# Central_Unit.net
KiCad netlist of a schematic drawn in Altium Designer
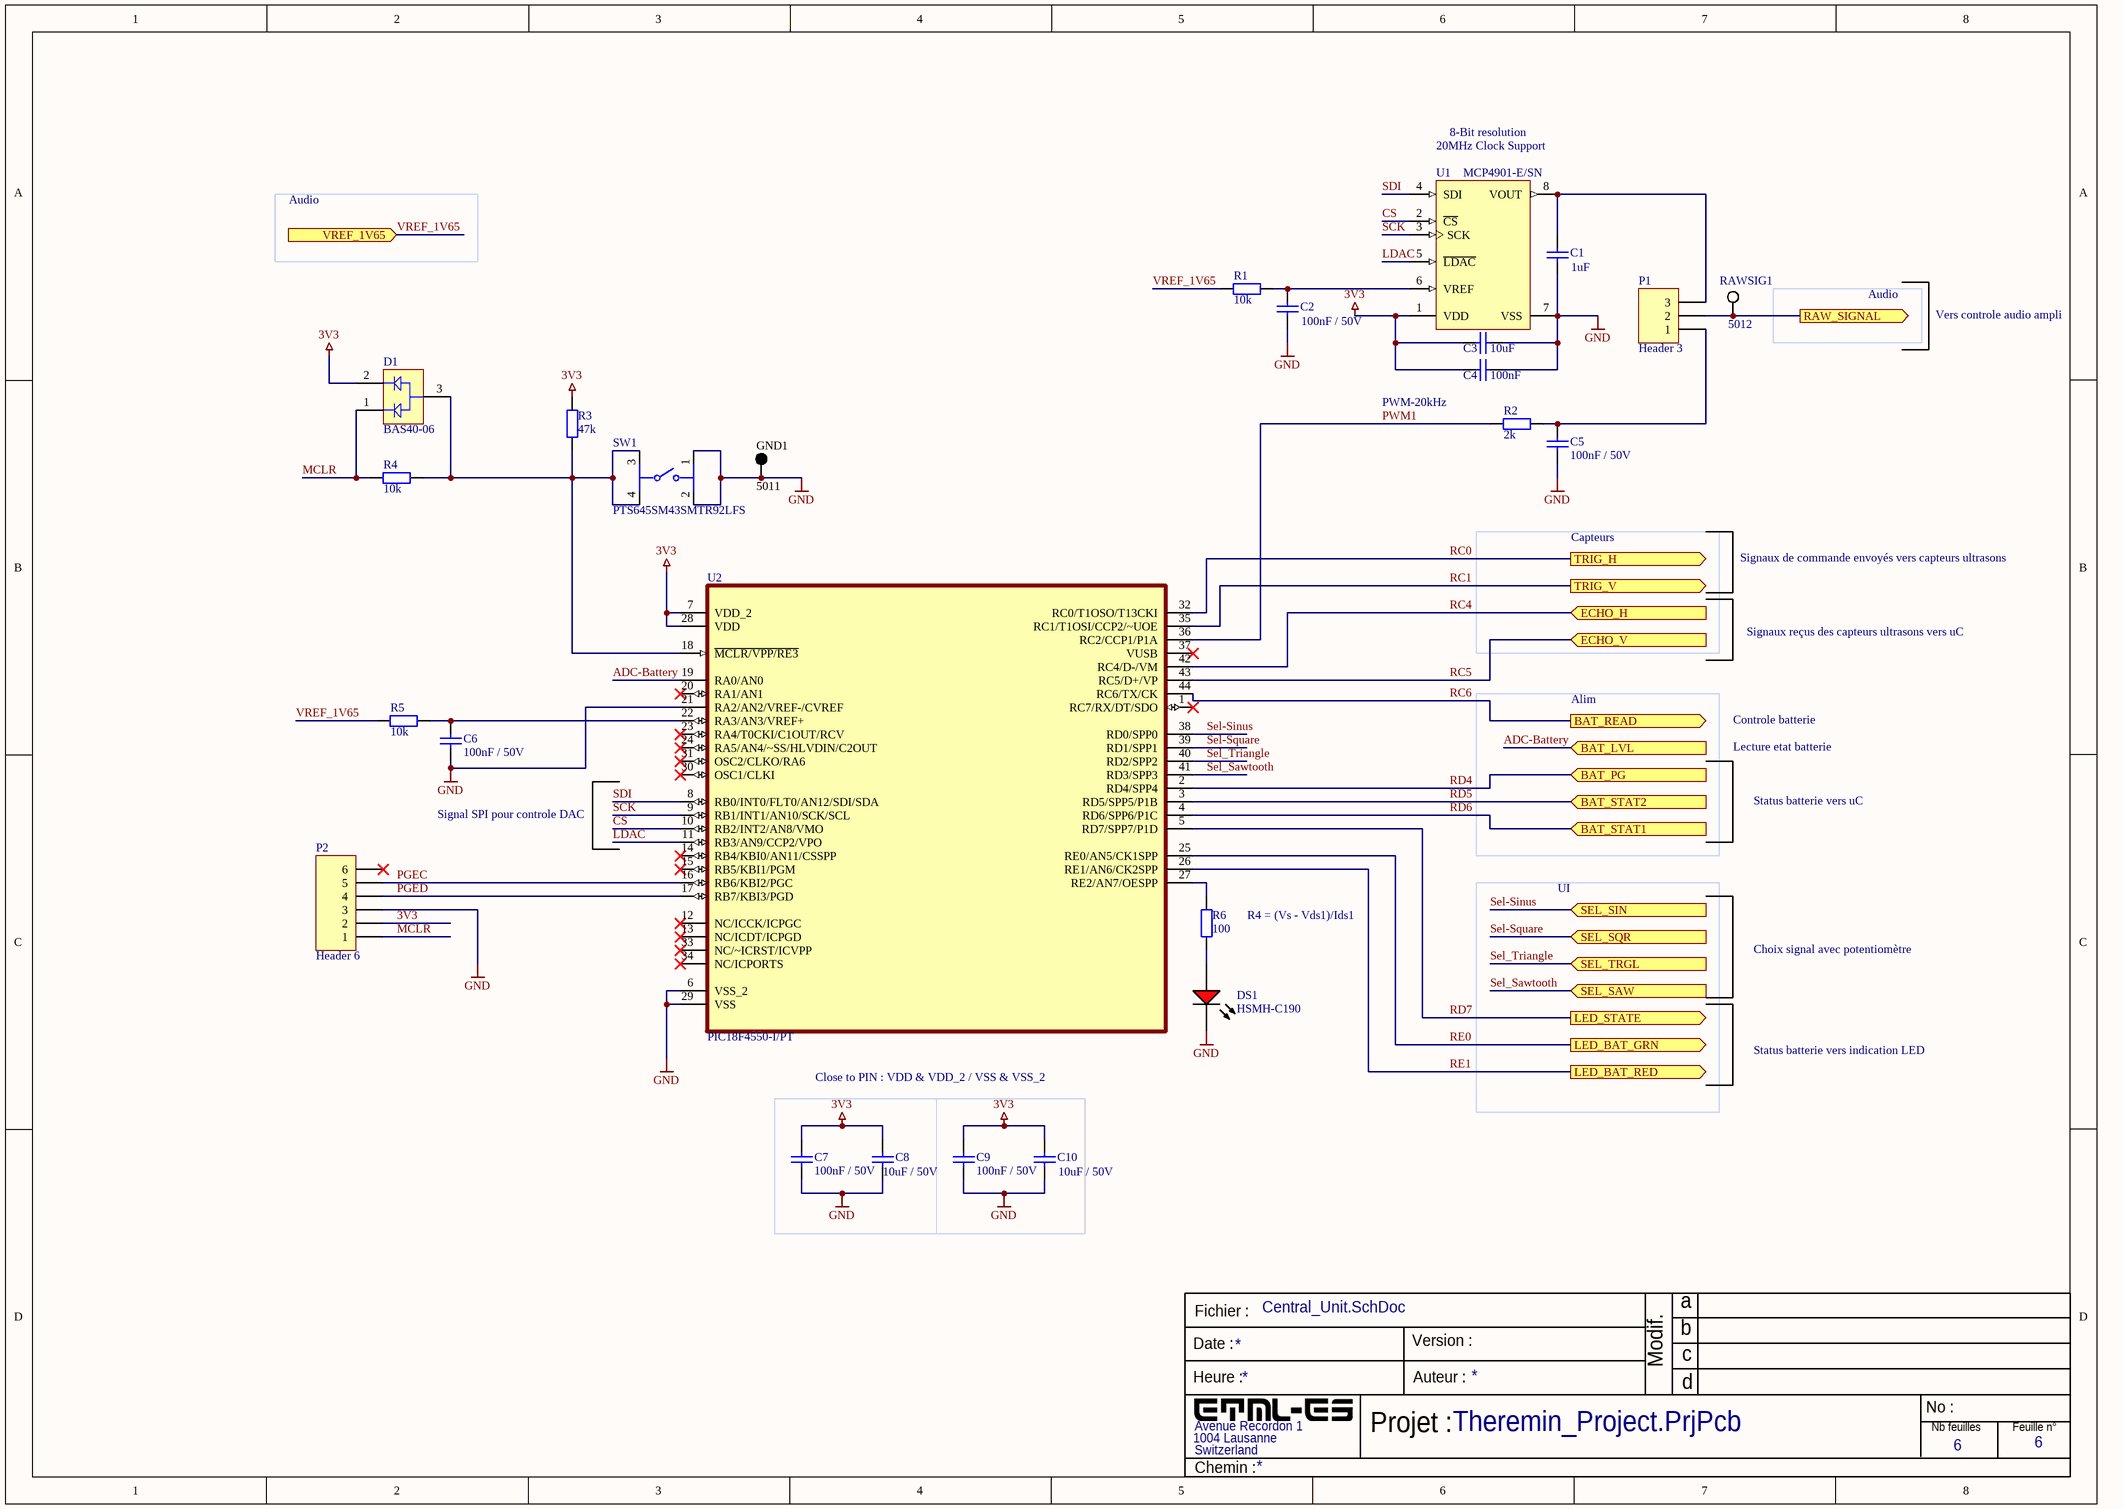
[diagram p0: Central_Unit.SchDoc]

(export (version "E")
  (design (tool "Eeschema 10.0.6"))
  (components
    (comp (ref "C1")
      (value "1uF")
      (footprint "CAPC0805")
      (description "Capacitor")
      (fields (field (name "PUBLISHER") "Altium Limited"))
      (libsource (lib "Miscellaneous Devices") (part "Cap"))
    )
    (comp (ref "C2")
      (value "100nF / 50V")
      (footprint "CAPC0805")
      (description "Capacitor")
      (fields (field (name "PUBLISHER") "Altium Limited"))
      (libsource (lib "Miscellaneous Devices") (part "Cap"))
    )
    (comp (ref "C3")
      (value "10uF")
      (footprint "CAPC0805")
      (description "Capacitor")
      (fields (field (name "PUBLISHER") "Altium Limited"))
      (libsource (lib "Miscellaneous Devices") (part "Cap"))
    )
    (comp (ref "C4")
      (value "100nF")
      (footprint "CAPC0805")
      (description "Capacitor")
      (fields (field (name "PUBLISHER") "Altium Limited"))
      (libsource (lib "Miscellaneous Devices") (part "Cap"))
    )
    (comp (ref "C5")
      (value "100nF / 50V")
      (footprint "CAPC0805")
      (description "Capacitor")
      (fields (field (name "PUBLISHER") "Altium Limited"))
      (libsource (lib "Miscellaneous Devices") (part "Cap"))
    )
    (comp (ref "C6")
      (value "100nF / 50V")
      (footprint "CAPC0805")
      (description "Capacitor")
      (fields (field (name "PUBLISHER") "Altium Limited"))
      (libsource (lib "Miscellaneous Devices") (part "Cap"))
    )
    (comp (ref "C7")
      (value "100nF / 50V")
      (footprint "CAPC0805")
      (description "Capacitor")
      (fields (field (name "PUBLISHER") "Altium Limited"))
      (libsource (lib "Miscellaneous Devices") (part "Cap"))
    )
    (comp (ref "C8")
      (value "10uF / 50V")
      (footprint "CAPC0805")
      (description "Capacitor")
      (fields (field (name "PUBLISHER") "Altium Limited"))
      (libsource (lib "Miscellaneous Devices") (part "Cap"))
    )
    (comp (ref "C9")
      (value "100nF / 50V")
      (footprint "CAPC0805")
      (description "Capacitor")
      (fields (field (name "PUBLISHER") "Altium Limited"))
      (libsource (lib "Miscellaneous Devices") (part "Cap"))
    )
    (comp (ref "C10")
      (value "10uF / 50V")
      (footprint "CAPC0805")
      (description "Capacitor")
      (fields (field (name "PUBLISHER") "Altium Limited"))
      (libsource (lib "Miscellaneous Devices") (part "Cap"))
    )
    (comp (ref "D1")
      (value "BAS40-06")
      (footprint "INF-SOT23_M")
      (description "Silicon Schottky Diode, -55 to 150 degC, SOT23, Reel, Green")
      (fields (field (name "MANUFACTURER") "Infineon"))
      (libsource (lib "Altium Content Vault") (part "INF-D_K1K2A3-3"))
    )
    (comp (ref "DS1")
      (value "HSMH-C190")
      (footprint "AVAG-HSMX-C190_V")
      (description "LED Uni-Color Red, 65 mW, 20 mA, -40 to 85 degC, 2-Pin SMD, RoHS, Tape and Reel")
      (libsource (lib "Altium Content Vault") (part "LED-RED-AK-2"))
    )
    (comp (ref "GND1")
      (value "5011")
      (footprint "KSTN-5011_V")
      (description "Test Point, Black, Through Hole, RoHS, Bulk")
      (fields (field (name "MANUFACTURER") "Keystone"))
      (libsource (lib "Altium Content Vault") (part "TESTPOINT_BLACK"))
    )
    (comp (ref "P1")
      (value "Header 3")
      (footprint "PIN-1x03_2.54")
      (description "Header, 3-Pin")
      (fields (field (name "PUBLISHER") "Altium Limited"))
      (libsource (lib "Miscellaneous Connectors") (part "Header 3"))
    )
    (comp (ref "P2")
      (value "Header 6")
      (footprint "PIN-1x06_2.54")
      (description "Header, 6-Pin")
      (fields (field (name "PUBLISHER") "Altium Limited"))
      (libsource (lib "Miscellaneous Connectors") (part "Header 6"))
    )
    (comp (ref "R1")
      (value "10k")
      (footprint "RESC0805")
      (description "Resistor")
      (libsource (lib "Support_BAT_1043") (part "RES"))
    )
    (comp (ref "R2")
      (value "2k")
      (footprint "RESC0805")
      (description "Resistor")
      (libsource (lib "Support_BAT_1043") (part "RES"))
    )
    (comp (ref "R3")
      (value "47k")
      (footprint "RESC0805")
      (description "Resistor")
      (libsource (lib "") (part "RES_1"))
    )
    (comp (ref "R4")
      (value "10k")
      (footprint "RESC0805")
      (description "Resistor")
      (libsource (lib "Support_BAT_1043") (part "RES"))
    )
    (comp (ref "R5")
      (value "10k")
      (footprint "RESC0805")
      (description "Resistor")
      (libsource (lib "Support_BAT_1043") (part "RES"))
    )
    (comp (ref "R6")
      (value "100")
      (footprint "RESC0805")
      (description "Resistor")
      (libsource (lib "") (part "RES_1"))
    )
    (comp (ref "RAWSIG1")
      (value "5012")
      (footprint "KSTN-5012_V")
      (description "Test Point, White, Through Hole, RoHS, Bulk")
      (fields (field (name "MANUFACTURER") "Keystone"))
      (libsource (lib "Altium Content Vault") (part "TESTPOINT_WHITE"))
    )
    (comp (ref "SW1")
      (value "PTS645SM43SMTR92LFS")
      (footprint "FP-PTS645SM43SMTR92LFS-MFG")
      (description "SWITCH TACTILE SPST-NO 0.05A 12V")
      (libsource (lib "Altium Content Vault") (part "1adf0dd01260c80cf25a44bfd6b99ba"))
    )
    (comp (ref "U1")
      (value "MCP4901-E/SN")
      (footprint "SOIC-SN8_N")
      (description "8-Bit DAC with SPI Interface, 8-Pin SOIC 150mil, Extended Temperature")
      (libsource (lib "Altium Content Vault") (part "CON-DAC-MCP4921-8"))
    )
    (comp (ref "U2")
      (value "PIC18F4550-I/PT")
      (footprint "TQFP80P1200X1200X120-44M")
      (description "PIC PICÂ® 18F Microcontroller IC 8-Bit 48MHz 32KB _16K x 16_ FLASH 44-TQFP _10x10_")
      (fields (field (name "MF") "Microchip"))
      (libsource (lib "PIC18F4550-I_PT") (part "PIC18F4550-I/PT"))
    )
  )
  (nets
    (net (code "1") (name "/ADC-Battery") (class "Default")
      (node (ref "U2") (pin "19") (pinfunction "RA0/AN0_19") (pintype "passive"))
    )
    (net (code "2") (name "/CS") (class "Default")
      (node (ref "U1") (pin "2") (pinfunction "~{CS}_2") (pintype "input"))
      (node (ref "U2") (pin "10") (pinfunction "RB2/INT2/AN8/VMO_10") (pintype "bidirectional"))
    )
    (net (code "3") (name "/LDAC") (class "Default")
      (node (ref "U1") (pin "5") (pinfunction "~{LDAC}_5") (pintype "input"))
      (node (ref "U2") (pin "11") (pinfunction "RB3/AN9/CCP2/VPO_11") (pintype "bidirectional"))
    )
    (net (code "4") (name "/MCLR") (class "Default")
      (node (ref "D1") (pin "1") (pinfunction "K1_1") (pintype "passive"))
      (node (ref "P2") (pin "1") (pinfunction "1_1") (pintype "passive"))
      (node (ref "R4") (pin "2") (pinfunction "2_2") (pintype "passive"))
    )
    (net (code "5") (name "/PGEC") (class "Default")
      (node (ref "P2") (pin "5") (pinfunction "5_5") (pintype "passive"))
      (node (ref "U2") (pin "16") (pinfunction "RB6/KBI2/PGC_16") (pintype "bidirectional"))
    )
    (net (code "6") (name "/PGED") (class "Default")
      (node (ref "P2") (pin "4") (pinfunction "4_4") (pintype "passive"))
      (node (ref "U2") (pin "17") (pinfunction "RB7/KBI3/PGD_17") (pintype "bidirectional"))
    )
    (net (code "7") (name "/PWM1") (class "Default")
      (node (ref "R2") (pin "2") (pinfunction "2_2") (pintype "passive"))
      (node (ref "U2") (pin "36") (pinfunction "RC2/CCP1/P1A_36") (pintype "passive"))
    )
    (net (code "8") (name "/RAW_SIGNAL") (class "Default")
      (node (ref "P1") (pin "2") (pinfunction "2_2") (pintype "passive"))
      (node (ref "RAWSIG1") (pin "1") (pinfunction "1_1") (pintype "passive"))
    )
    (net (code "9") (name "/RC0") (class "Default")
      (node (ref "U2") (pin "32") (pinfunction "RC0/T1OSO/T13CKI_32") (pintype "passive"))
    )
    (net (code "10") (name "/RC1") (class "Default")
      (node (ref "U2") (pin "35") (pinfunction "RC1/T1OSI/CCP2/~UOE_35") (pintype "passive"))
    )
    (net (code "11") (name "/RC4") (class "Default")
      (node (ref "U2") (pin "42") (pinfunction "RC4/D-/VM_42") (pintype "passive"))
    )
    (net (code "12") (name "/RC5") (class "Default")
      (node (ref "U2") (pin "43") (pinfunction "RC5/D+/VP_43") (pintype "passive"))
    )
    (net (code "13") (name "/RC6") (class "Default")
      (node (ref "U2") (pin "44") (pinfunction "RC6/TX/CK_44") (pintype "passive"))
    )
    (net (code "14") (name "/RD4") (class "Default")
      (node (ref "U2") (pin "2") (pinfunction "RD4/SPP4_2") (pintype "passive"))
    )
    (net (code "15") (name "/RD5") (class "Default")
      (node (ref "U2") (pin "3") (pinfunction "RD5/SPP5/P1B_3") (pintype "passive"))
    )
    (net (code "16") (name "/RD6") (class "Default")
      (node (ref "U2") (pin "4") (pinfunction "RD6/SPP6/P1C_4") (pintype "passive"))
    )
    (net (code "17") (name "/RD7") (class "Default")
      (node (ref "U2") (pin "5") (pinfunction "RD7/SPP7/P1D_5") (pintype "passive"))
    )
    (net (code "18") (name "/RE0") (class "Default")
      (node (ref "U2") (pin "25") (pinfunction "RE0/AN5/CK1SPP_25") (pintype "passive"))
    )
    (net (code "19") (name "/RE1") (class "Default")
      (node (ref "U2") (pin "26") (pinfunction "RE1/AN6/CK2SPP_26") (pintype "passive"))
    )
    (net (code "20") (name "/SCK") (class "Default")
      (node (ref "U1") (pin "3") (pinfunction "SCK_3") (pintype "input"))
      (node (ref "U2") (pin "9") (pinfunction "RB1/INT1/AN10/SCK/SCL_9") (pintype "bidirectional"))
    )
    (net (code "21") (name "/SDI") (class "Default")
      (node (ref "U1") (pin "4") (pinfunction "SDI_4") (pintype "input"))
      (node (ref "U2") (pin "8") (pinfunction "RB0/INT0/FLT0/AN12/SDI/SDA_8") (pintype "bidirectional"))
    )
    (net (code "22") (name "/Sel-Sinus") (class "Default")
      (node (ref "U2") (pin "38") (pinfunction "RD0/SPP0_38") (pintype "passive"))
    )
    (net (code "23") (name "/Sel-Square") (class "Default")
      (node (ref "U2") (pin "39") (pinfunction "RD1/SPP1_39") (pintype "passive"))
    )
    (net (code "24") (name "/Sel_Sawtooth") (class "Default")
      (node (ref "U2") (pin "41") (pinfunction "RD3/SPP3_41") (pintype "passive"))
    )
    (net (code "25") (name "/Sel_Triangle") (class "Default")
      (node (ref "U2") (pin "40") (pinfunction "RD2/SPP2_40") (pintype "passive"))
    )
    (net (code "26") (name "/VREF_1V65") (class "Default")
      (node (ref "R1") (pin "2") (pinfunction "2_2") (pintype "passive"))
      (node (ref "R5") (pin "2") (pinfunction "2_2") (pintype "passive"))
    )
    (net (code "27") (name "3V3") (class "Default")
      (node (ref "C10") (pin "1") (pinfunction "1_1") (pintype "passive"))
      (node (ref "C3") (pin "1") (pinfunction "1_1") (pintype "passive"))
      (node (ref "C4") (pin "1") (pinfunction "1_1") (pintype "passive"))
      (node (ref "C7") (pin "1") (pinfunction "1_1") (pintype "passive"))
      (node (ref "C8") (pin "1") (pinfunction "1_1") (pintype "passive"))
      (node (ref "C9") (pin "1") (pinfunction "1_1") (pintype "passive"))
      (node (ref "D1") (pin "2") (pinfunction "K2_2") (pintype "passive"))
      (node (ref "P2") (pin "2") (pinfunction "2_2") (pintype "passive"))
      (node (ref "R3") (pin "1") (pinfunction "1_1") (pintype "passive"))
      (node (ref "U1") (pin "1") (pinfunction "VDD_1") (pintype "power_in"))
      (node (ref "U2") (pin "28") (pinfunction "VDD_28") (pintype "power_in"))
      (node (ref "U2") (pin "7") (pinfunction "VDD_2_7") (pintype "power_in"))
    )
    (net (code "28") (name "GND") (class "Default")
      (node (ref "C1") (pin "2") (pinfunction "2_2") (pintype "passive"))
      (node (ref "C10") (pin "2") (pinfunction "2_2") (pintype "passive"))
      (node (ref "C2") (pin "2") (pinfunction "2_2") (pintype "passive"))
      (node (ref "C3") (pin "2") (pinfunction "2_2") (pintype "passive"))
      (node (ref "C4") (pin "2") (pinfunction "2_2") (pintype "passive"))
      (node (ref "C5") (pin "2") (pinfunction "2_2") (pintype "passive"))
      (node (ref "C6") (pin "2") (pinfunction "2_2") (pintype "passive"))
      (node (ref "C7") (pin "2") (pinfunction "2_2") (pintype "passive"))
      (node (ref "C8") (pin "2") (pinfunction "2_2") (pintype "passive"))
      (node (ref "C9") (pin "2") (pinfunction "2_2") (pintype "passive"))
      (node (ref "DS1") (pin "2") (pinfunction "K_2") (pintype "passive"))
      (node (ref "GND1") (pin "1") (pinfunction "1_1") (pintype "passive"))
      (node (ref "P2") (pin "3") (pinfunction "3_3") (pintype "passive"))
      (node (ref "SW1") (pin "1") (pinfunction "1_1") (pintype "passive"))
      (node (ref "SW1") (pin "2") (pinfunction "2_2") (pintype "passive"))
      (node (ref "U1") (pin "7") (pinfunction "VSS_7") (pintype "power_in"))
      (node (ref "U2") (pin "21") (pinfunction "RA2/AN2/VREF-/CVREF_21") (pintype "passive"))
      (node (ref "U2") (pin "29") (pinfunction "VSS_29") (pintype "power_in"))
      (node (ref "U2") (pin "6") (pinfunction "VSS_2_6") (pintype "power_in"))
    )
    (net (code "29") (name "Net-(C5-Pad1)") (class "Default")
      (node (ref "C5") (pin "1") (pinfunction "1_1") (pintype "passive"))
      (node (ref "P1") (pin "1") (pinfunction "1_1") (pintype "passive"))
      (node (ref "R2") (pin "1") (pinfunction "1_1") (pintype "passive"))
    )
    (net (code "30") (name "Net-(D1-A)") (class "Default")
      (node (ref "D1") (pin "3") (pinfunction "A_3") (pintype "passive"))
      (node (ref "R3") (pin "2") (pinfunction "2_2") (pintype "passive"))
      (node (ref "R4") (pin "1") (pinfunction "1_1") (pintype "passive"))
      (node (ref "SW1") (pin "3") (pinfunction "3_3") (pintype "passive"))
      (node (ref "SW1") (pin "4") (pinfunction "4_4") (pintype "passive"))
      (node (ref "U2") (pin "18") (pinfunction "~{MCLR/VPP/RE3}_18") (pintype "input"))
    )
    (net (code "31") (name "Net-(DS1-A)") (class "Default")
      (node (ref "DS1") (pin "1") (pinfunction "A_1") (pintype "passive"))
      (node (ref "R6") (pin "2") (pinfunction "2_2") (pintype "passive"))
    )
    (net (code "32") (name "Net-(U1-VOUT)") (class "Default")
      (node (ref "C1") (pin "1") (pinfunction "1_1") (pintype "passive"))
      (node (ref "P1") (pin "3") (pinfunction "3_3") (pintype "passive"))
      (node (ref "U1") (pin "8") (pinfunction "VOUT_8") (pintype "output"))
    )
    (net (code "33") (name "Net-(U1-VREF)") (class "Default")
      (node (ref "C2") (pin "1") (pinfunction "1_1") (pintype "passive"))
      (node (ref "R1") (pin "1") (pinfunction "1_1") (pintype "passive"))
      (node (ref "U1") (pin "6") (pinfunction "VREF_6") (pintype "input"))
    )
    (net (code "34") (name "Net-(U2-RA3{slash}AN3{slash}VREF+)") (class "Default")
      (node (ref "C6") (pin "1") (pinfunction "1_1") (pintype "passive"))
      (node (ref "R5") (pin "1") (pinfunction "1_1") (pintype "passive"))
      (node (ref "U2") (pin "22") (pinfunction "RA3/AN3/VREF+_22") (pintype "bidirectional"))
    )
    (net (code "35") (name "Net-(U2-RE2{slash}AN7{slash}OESPP)") (class "Default")
      (node (ref "R6") (pin "1") (pinfunction "1_1") (pintype "passive"))
      (node (ref "U2") (pin "27") (pinfunction "RE2/AN7/OESPP_27") (pintype "passive"))
    )
    (net (code "36") (name "unconnected-(P2-Pad6)") (class "Default")
      (node (ref "P2") (pin "6") (pinfunction "6_6") (pintype "passive+no_connect"))
    )
    (net (code "37") (name "unconnected-(U2-NC{slash}ICCK{slash}ICPGC-Pad12)") (class "Default")
      (node (ref "U2") (pin "12") (pinfunction "NC/ICCK/ICPGC_12") (pintype "passive+no_connect"))
    )
    (net (code "38") (name "unconnected-(U2-NC{slash}ICDT{slash}ICPGD-Pad13)") (class "Default")
      (node (ref "U2") (pin "13") (pinfunction "NC/ICDT/ICPGD_13") (pintype "passive+no_connect"))
    )
    (net (code "39") (name "unconnected-(U2-NC{slash}ICPORTS-Pad34)") (class "Default")
      (node (ref "U2") (pin "34") (pinfunction "NC/ICPORTS_34") (pintype "passive+no_connect"))
    )
    (net (code "40") (name "unconnected-(U2-NC{slash}~ICRST{slash}ICVPP-Pad33)") (class "Default")
      (node (ref "U2") (pin "33") (pinfunction "NC/~ICRST/ICVPP_33") (pintype "passive+no_connect"))
    )
    (net (code "41") (name "unconnected-(U2-OSC1{slash}CLKI-Pad30)") (class "Default")
      (node (ref "U2") (pin "30") (pinfunction "OSC1/CLKI_30") (pintype "bidirectional+no_connect"))
    )
    (net (code "42") (name "unconnected-(U2-OSC2{slash}CLKO{slash}RA6-Pad31)") (class "Default")
      (node (ref "U2") (pin "31") (pinfunction "OSC2/CLKO/RA6_31") (pintype "bidirectional+no_connect"))
    )
    (net (code "43") (name "unconnected-(U2-RA1{slash}AN1-Pad20)") (class "Default")
      (node (ref "U2") (pin "20") (pinfunction "RA1/AN1_20") (pintype "bidirectional+no_connect"))
    )
    (net (code "44") (name "unconnected-(U2-RA4{slash}T0CKI{slash}C1OUT{slash}RCV-Pad23)") (class "Default")
      (node (ref "U2") (pin "23") (pinfunction "RA4/T0CKI/C1OUT/RCV_23") (pintype "bidirectional+no_connect"))
    )
    (net (code "45") (name "unconnected-(U2-RA5{slash}AN4{slash}~SS{slash}HLVDIN{slash}C2OUT-Pad24)") (class "Default")
      (node (ref "U2") (pin "24") (pinfunction "RA5/AN4/~SS/HLVDIN/C2OUT_24") (pintype "bidirectional+no_connect"))
    )
    (net (code "46") (name "unconnected-(U2-RB4{slash}KBI0{slash}AN11{slash}CSSPP-Pad14)") (class "Default")
      (node (ref "U2") (pin "14") (pinfunction "RB4/KBI0/AN11/CSSPP_14") (pintype "bidirectional+no_connect"))
    )
    (net (code "47") (name "unconnected-(U2-RB5{slash}KBI1{slash}PGM-Pad15)") (class "Default")
      (node (ref "U2") (pin "15") (pinfunction "RB5/KBI1/PGM_15") (pintype "bidirectional+no_connect"))
    )
    (net (code "48") (name "unconnected-(U2-RC7{slash}RX{slash}DT{slash}SDO-Pad1)") (class "Default")
      (node (ref "U2") (pin "1") (pinfunction "RC7/RX/DT/SDO_1") (pintype "bidirectional+no_connect"))
    )
    (net (code "49") (name "unconnected-(U2-VUSB-Pad37)") (class "Default")
      (node (ref "U2") (pin "37") (pinfunction "VUSB_37") (pintype "passive+no_connect"))
    )
  )
)
